# Sheet1.net
KiCad netlist of a schematic drawn in Altium Designer
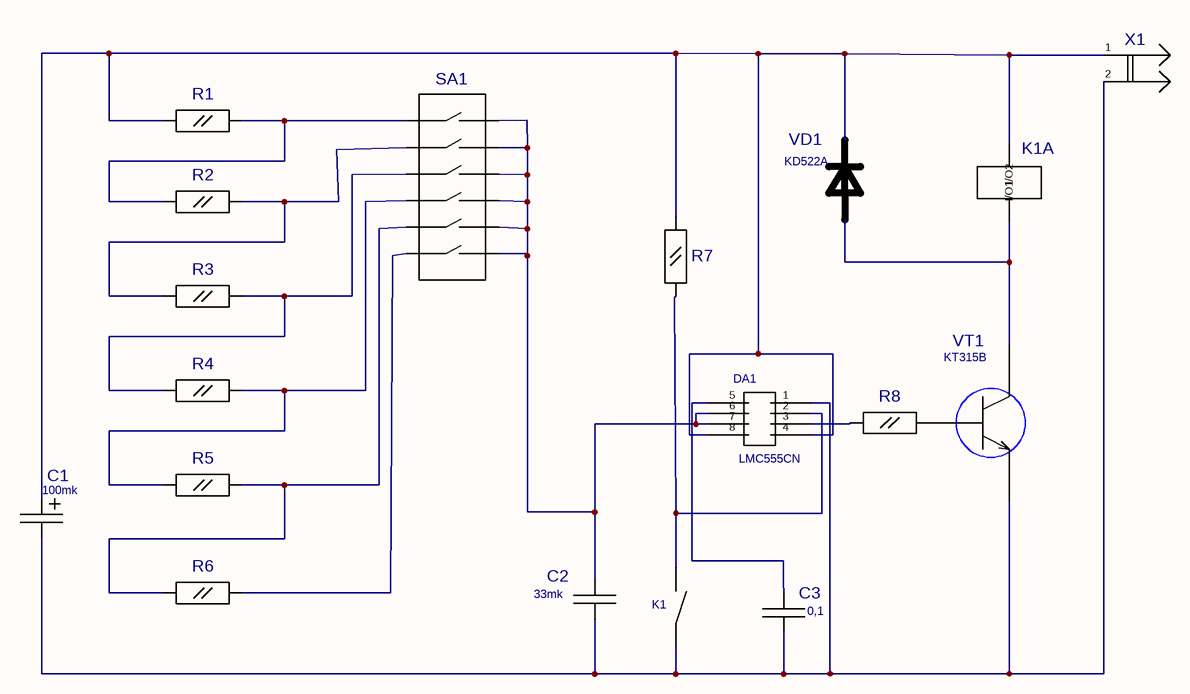
[diagram p0: Sheet1.SCHDOC]

(export (version "E")
  (design (tool "Eeschema 10.0.6"))
  (components
    (comp (ref "C1")
      (value "100mk")
      (footprint "ECR-8")
      (description "ECR-8")
      (libsource (lib "*") (part "ECR-8"))
    )
    (comp (ref "C2")
      (value "33mk")
      (footprint "1017-B3R")
      (description "1017-B3R")
      (libsource (lib "*") (part "1017-B3R"))
    )
    (comp (ref "C3")
      (value "0,1")
      (footprint "1017-B3R")
      (description "1017-B3R")
      (libsource (lib "*") (part "1017-B3R"))
    )
    (comp (ref "DA1") (value "LMC555CN") (footprint "LMC555CN") (libsource (lib "*") (part "LMC555CN")))
    (comp (ref "K1")
      (value "РЕЛЕ-6")
      (footprint "RELE6")
      (description "РЕЛЕ-6")
      (libsource (lib "*") (part "РЕЛЕ-6"))
    )
    (comp (ref "R1")
      (value "C2-33H-0.125W_OLD_UGO")
      (footprint "C2-33H-0.125W")
      (fields (field (name "AUTOR") "pcbdesigner.ru"))
      (libsource (lib "*") (part "C2-33H-0.125W_OLD_UGO"))
    )
    (comp (ref "R2")
      (value "C2-33H-0.125W_OLD_UGO")
      (footprint "C2-33H-0.125W")
      (fields (field (name "AUTOR") "pcbdesigner.ru"))
      (libsource (lib "*") (part "C2-33H-0.125W_OLD_UGO"))
    )
    (comp (ref "R3")
      (value "C2-33H-0.125W_OLD_UGO")
      (footprint "C2-33H-0.125W")
      (fields (field (name "AUTOR") "pcbdesigner.ru"))
      (libsource (lib "*") (part "C2-33H-0.125W_OLD_UGO"))
    )
    (comp (ref "R4")
      (value "C2-33H-0.125W_OLD_UGO")
      (footprint "C2-33H-0.125W")
      (fields (field (name "AUTOR") "pcbdesigner.ru"))
      (libsource (lib "*") (part "C2-33H-0.125W_OLD_UGO"))
    )
    (comp (ref "R5")
      (value "C2-33H-0.125W_OLD_UGO")
      (footprint "C2-33H-0.125W")
      (fields (field (name "AUTOR") "pcbdesigner.ru"))
      (libsource (lib "*") (part "C2-33H-0.125W_OLD_UGO"))
    )
    (comp (ref "R6")
      (value "C2-33H-0.125W_OLD_UGO")
      (footprint "C2-33H-0.125W")
      (fields (field (name "AUTOR") "pcbdesigner.ru"))
      (libsource (lib "*") (part "C2-33H-0.125W_OLD_UGO"))
    )
    (comp (ref "R7")
      (value "C2-33H-0.125W_OLD_UGO")
      (footprint "C2-33H-0.125W")
      (description "C2-33H-0.125W_OLD_UGO_VARIANT_1")
      (fields (field (name "AUTOR") "pcbdesigner.ru"))
      (libsource (lib "*") (part "C2-33H-0.125W_OLD_UGO"))
    )
    (comp (ref "R8")
      (value "C2-33H-0.125W_OLD_UGO")
      (footprint "C2-33H-0.125W")
      (fields (field (name "AUTOR") "pcbdesigner.ru"))
      (libsource (lib "*") (part "C2-33H-0.125W_OLD_UGO"))
    )
    (comp (ref "SA1")
      (value "DS1040-6")
      (footprint "DS1040-6")
      (fields (field (name "AUTHOR") "pcbdesigner.ru"))
      (libsource (lib "*") (part "DS1040-6"))
    )
    (comp (ref "VD1")
      (value "KD522A")
      (footprint "КД521(522)")
      (description "КД522А")
      (libsource (lib "*") (part "КД522А"))
    )
    (comp (ref "VT1")
      (value "KT315B")
      (footprint "KT13")
      (description "КТ315В")
      (libsource (lib "*") (part "КТ315В"))
    )
    (comp (ref "X1") (value "2XR") (footprint "2XR") (libsource (lib "*") (part "2XR")))
  )
  (nets
    (net (code "1") (name "Net-(C1-I{slash}OA)") (class "Default")
      (node (ref "C1") (pin "1") (pinfunction "I/OA_1") (pintype "passive"))
      (node (ref "DA1") (pin "4") (pintype "passive"))
      (node (ref "DA1") (pin "8") (pintype "passive"))
      (node (ref "K1") (pin "2") (pinfunction "I/O2_2") (pintype "passive"))
      (node (ref "R1") (pin "1") (pinfunction "1_1") (pintype "passive"))
      (node (ref "R7") (pin "2") (pinfunction "2_2") (pintype "passive"))
      (node (ref "VD1") (pin "2") (pinfunction "K_2") (pintype "passive"))
      (node (ref "X1") (pin "1") (pinfunction "I/O1_1") (pintype "passive"))
    )
    (net (code "2") (name "Net-(C1-I{slash}OB)") (class "Default")
      (node (ref "C1") (pin "2") (pinfunction "I/OB_2") (pintype "passive"))
      (node (ref "C2") (pin "2") (pinfunction "I/OB_2") (pintype "passive"))
      (node (ref "C3") (pin "2") (pinfunction "I/OB_2") (pintype "passive"))
      (node (ref "DA1") (pin "1") (pintype "passive"))
      (node (ref "K1") (pin "3") (pinfunction "I/O1_3") (pintype "passive"))
      (node (ref "VT1") (pin "1") (pinfunction "E_1") (pintype "passive"))
      (node (ref "X1") (pin "2") (pinfunction "I/O2_2") (pintype "passive"))
    )
    (net (code "3") (name "Net-(C2-I{slash}OA)") (class "Default")
      (node (ref "C2") (pin "1") (pinfunction "I/OA_1") (pintype "passive"))
      (node (ref "DA1") (pin "6") (pintype "passive"))
      (node (ref "DA1") (pin "7") (pintype "passive"))
      (node (ref "SA1") (pin "10") (pinfunction "10_10") (pintype "passive"))
      (node (ref "SA1") (pin "11") (pinfunction "11_11") (pintype "passive"))
      (node (ref "SA1") (pin "12") (pinfunction "12_12") (pintype "passive"))
      (node (ref "SA1") (pin "7") (pinfunction "7_7") (pintype "passive"))
      (node (ref "SA1") (pin "8") (pinfunction "8_8") (pintype "passive"))
      (node (ref "SA1") (pin "9") (pinfunction "9_9") (pintype "passive"))
    )
    (net (code "4") (name "Net-(C3-I{slash}OA)") (class "Default")
      (node (ref "C3") (pin "1") (pinfunction "I/OA_1") (pintype "passive"))
      (node (ref "DA1") (pin "5") (pintype "passive"))
    )
    (net (code "5") (name "Net-(DA1-Pad3)") (class "Default")
      (node (ref "DA1") (pin "3") (pintype "passive"))
      (node (ref "R8") (pin "1") (pinfunction "1_1") (pintype "passive"))
    )
    (net (code "6") (name "Net-(K1A-I{slash}O1)") (class "Default")
      (node (ref "K1") (pin "1") (pinfunction "I/O1_1") (pintype "passive"))
      (node (ref "VD1") (pin "1") (pinfunction "A_1") (pintype "passive"))
      (node (ref "VT1") (pin "3") (pinfunction "K_3") (pintype "passive"))
    )
    (net (code "7") (name "Net-(K1B-I{slash}O2)") (class "Default")
      (node (ref "DA1") (pin "2") (pintype "passive"))
      (node (ref "K1") (pin "4") (pinfunction "I/O2_4") (pintype "passive"))
      (node (ref "R7") (pin "1") (pinfunction "1_1") (pintype "passive"))
    )
    (net (code "8") (name "Net-(R1-Pad2)") (class "Default")
      (node (ref "R1") (pin "2") (pinfunction "2_2") (pintype "passive"))
      (node (ref "R2") (pin "1") (pinfunction "1_1") (pintype "passive"))
      (node (ref "SA1") (pin "1") (pinfunction "1_1") (pintype "passive"))
    )
    (net (code "9") (name "Net-(R2-Pad2)") (class "Default")
      (node (ref "R2") (pin "2") (pinfunction "2_2") (pintype "passive"))
      (node (ref "R3") (pin "1") (pinfunction "1_1") (pintype "passive"))
      (node (ref "SA1") (pin "2") (pinfunction "2_2") (pintype "passive"))
    )
    (net (code "10") (name "Net-(R3-Pad2)") (class "Default")
      (node (ref "R3") (pin "2") (pinfunction "2_2") (pintype "passive"))
      (node (ref "R4") (pin "1") (pinfunction "1_1") (pintype "passive"))
      (node (ref "SA1") (pin "3") (pinfunction "3_3") (pintype "passive"))
    )
    (net (code "11") (name "Net-(R4-Pad2)") (class "Default")
      (node (ref "R4") (pin "2") (pinfunction "2_2") (pintype "passive"))
      (node (ref "R5") (pin "1") (pinfunction "1_1") (pintype "passive"))
      (node (ref "SA1") (pin "4") (pinfunction "4_4") (pintype "passive"))
    )
    (net (code "12") (name "Net-(R5-Pad2)") (class "Default")
      (node (ref "R5") (pin "2") (pinfunction "2_2") (pintype "passive"))
      (node (ref "R6") (pin "1") (pinfunction "1_1") (pintype "passive"))
      (node (ref "SA1") (pin "5") (pinfunction "5_5") (pintype "passive"))
    )
    (net (code "13") (name "Net-(R6-Pad2)") (class "Default")
      (node (ref "R6") (pin "2") (pinfunction "2_2") (pintype "passive"))
      (node (ref "SA1") (pin "6") (pinfunction "6_6") (pintype "passive"))
    )
    (net (code "14") (name "Net-(VT1-B)") (class "Default")
      (node (ref "R8") (pin "2") (pinfunction "2_2") (pintype "passive"))
      (node (ref "VT1") (pin "2") (pinfunction "B_2") (pintype "passive"))
    )
  )
)
